# PiPico.net
KiCad netlist of a schematic drawn in Altium Designer
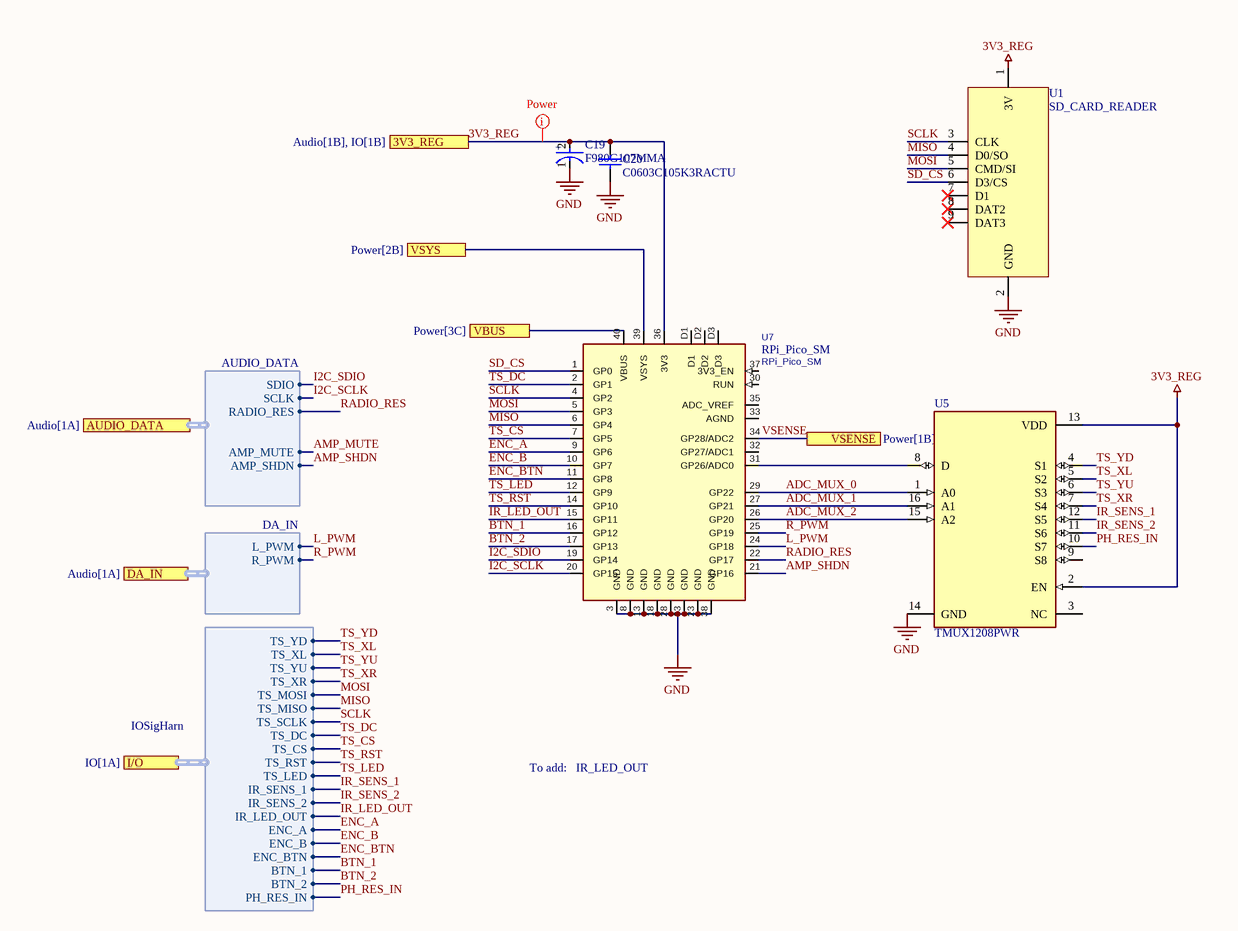
[diagram p0: PiPico.SchDoc]

(export (version "E")
  (design (tool "Eeschema 10.0.6"))
  (components
    (comp (ref "C19")
      (value "F980G107MMA")
      (footprint "FP-F98M-MFG")
      (description "CAP TANT 100UF 20% 4V 0603")
      (fields
        (field (name "OCTOPART") "https://octopart.com/f980g107mma-avx-28870482")
        (field (name "MANUFACTURER") "AVX Corporation")
      )
      (libsource (lib "Altium Content Vault") (part "cf48714ba7e38822c1575c7ec0b6d1f"))
    )
    (comp (ref "C20")
      (value "C0603C105K3RACTU")
      (footprint "CAPC1608X87X35LL15T15")
      (fields (field (name "MANUFACTURER") "Kemet"))
      (libsource (lib "Altium Content Vault") (part "CAP"))
    )
    (comp (ref "U1")
      (value "SD_CARD_READER")
      (footprint "6-pin Header (Generic)")
      (libsource (lib "ECE299_PCB") (part "SD_CARD_READER"))
    )
    (comp (ref "U5")
      (value "TMUX1208PWR")
      (footprint "FP-PW0016A-IPC_A")
      (description "IC SWITCH SINGLE 16TSSOP")
      (libsource (lib "Altium Content Vault") (part "3fc1eebd4caa5623a46538ca285a60d"))
    )
    (comp (ref "U7")
      (value "RPi_Pico_SM")
      (footprint "RPi_Pico_SM")
      (fields (field (name "ALTIUM_VALUE") "RPi_Pico_SM"))
      (libsource (lib "IlamStuff") (part "RPi_Pico_SM"))
    )
  )
  (nets
    (net (code "4") (name "/ADC_MUX_0") (class "Default")
      (node (ref "U5") (pin "1") (pinfunction "A0_1") (pintype "input"))
      (node (ref "U7") (pin "29") (pinfunction "GP22_29") (pintype "bidirectional"))
    )
    (net (code "5") (name "/ADC_MUX_1") (class "Default")
      (node (ref "U5") (pin "16") (pinfunction "A1_16") (pintype "input"))
      (node (ref "U7") (pin "27") (pinfunction "GP21_27") (pintype "bidirectional"))
    )
    (net (code "6") (name "/ADC_MUX_2") (class "Default")
      (node (ref "U5") (pin "15") (pinfunction "A2_15") (pintype "input"))
      (node (ref "U7") (pin "26") (pinfunction "GP20_26") (pintype "bidirectional"))
    )
    (net (code "8") (name "/AMP_SHDN") (class "Default")
      (node (ref "U7") (pin "21") (pinfunction "GP16_21") (pintype "bidirectional"))
    )
    (net (code "9") (name "/BTN_1") (class "Default")
      (node (ref "U7") (pin "16") (pinfunction "GP12_16") (pintype "bidirectional"))
    )
    (net (code "10") (name "/BTN_2") (class "Default")
      (node (ref "U7") (pin "17") (pinfunction "GP13_17") (pintype "bidirectional"))
    )
    (net (code "11") (name "/ENC_A") (class "Default")
      (node (ref "U7") (pin "9") (pinfunction "GP6_9") (pintype "bidirectional"))
    )
    (net (code "12") (name "/ENC_B") (class "Default")
      (node (ref "U7") (pin "10") (pinfunction "GP7_10") (pintype "bidirectional"))
    )
    (net (code "13") (name "/ENC_BTN") (class "Default")
      (node (ref "U7") (pin "11") (pinfunction "GP8_11") (pintype "bidirectional"))
    )
    (net (code "14") (name "/I2C_SCLK") (class "Default")
      (node (ref "U7") (pin "20") (pinfunction "GP15_20") (pintype "bidirectional"))
    )
    (net (code "15") (name "/I2C_SDIO") (class "Default")
      (node (ref "U7") (pin "19") (pinfunction "GP14_19") (pintype "bidirectional"))
    )
    (net (code "16") (name "/IR_LED_OUT") (class "Default")
      (node (ref "U7") (pin "15") (pinfunction "GP11_15") (pintype "bidirectional"))
    )
    (net (code "17") (name "/IR_SENS_1") (class "Default")
      (node (ref "U5") (pin "12") (pinfunction "S5_12") (pintype "bidirectional"))
    )
    (net (code "18") (name "/IR_SENS_2") (class "Default")
      (node (ref "U5") (pin "11") (pinfunction "S6_11") (pintype "bidirectional"))
    )
    (net (code "19") (name "/L_PWM") (class "Default")
      (node (ref "U7") (pin "24") (pinfunction "GP18_24") (pintype "bidirectional"))
    )
    (net (code "20") (name "/MISO") (class "Default")
      (node (ref "U1") (pin "4") (pinfunction "D0/SO_4") (pintype "passive"))
      (node (ref "U7") (pin "6") (pinfunction "GP4_6") (pintype "bidirectional"))
    )
    (net (code "21") (name "/MOSI") (class "Default")
      (node (ref "U1") (pin "5") (pinfunction "CMD/SI_5") (pintype "passive"))
      (node (ref "U7") (pin "5") (pinfunction "GP3_5") (pintype "bidirectional"))
    )
    (net (code "22") (name "/PH_RES_IN") (class "Default")
      (node (ref "U5") (pin "10") (pinfunction "S7_10") (pintype "bidirectional"))
    )
    (net (code "23") (name "/RADIO_RES") (class "Default")
      (node (ref "U7") (pin "22") (pinfunction "GP17_22") (pintype "bidirectional"))
    )
    (net (code "24") (name "/R_PWM") (class "Default")
      (node (ref "U7") (pin "25") (pinfunction "GP19_25") (pintype "bidirectional"))
    )
    (net (code "25") (name "/SCLK") (class "Default")
      (node (ref "U1") (pin "3") (pinfunction "CLK_3") (pintype "passive"))
      (node (ref "U7") (pin "4") (pinfunction "GP2_4") (pintype "bidirectional"))
    )
    (net (code "26") (name "/SD_CS") (class "Default")
      (node (ref "U1") (pin "6") (pinfunction "D3/CS_6") (pintype "passive"))
      (node (ref "U7") (pin "1") (pinfunction "GP0_1") (pintype "bidirectional"))
    )
    (net (code "27") (name "/TS_CS") (class "Default")
      (node (ref "U7") (pin "7") (pinfunction "GP5_7") (pintype "bidirectional"))
    )
    (net (code "28") (name "/TS_DC") (class "Default")
      (node (ref "U7") (pin "2") (pinfunction "GP1_2") (pintype "bidirectional"))
    )
    (net (code "29") (name "/TS_LED") (class "Default")
      (node (ref "U7") (pin "12") (pinfunction "GP9_12") (pintype "bidirectional"))
    )
    (net (code "30") (name "/TS_RST") (class "Default")
      (node (ref "U7") (pin "14") (pinfunction "GP10_14") (pintype "bidirectional"))
    )
    (net (code "31") (name "/TS_XL") (class "Default")
      (node (ref "U5") (pin "5") (pinfunction "S2_5") (pintype "bidirectional"))
    )
    (net (code "32") (name "/TS_XR") (class "Default")
      (node (ref "U5") (pin "7") (pinfunction "S4_7") (pintype "bidirectional"))
    )
    (net (code "33") (name "/TS_YD") (class "Default")
      (node (ref "U5") (pin "4") (pinfunction "S1_4") (pintype "bidirectional"))
    )
    (net (code "34") (name "/TS_YU") (class "Default")
      (node (ref "U5") (pin "6") (pinfunction "S3_6") (pintype "bidirectional"))
    )
    (net (code "35") (name "/VBUS") (class "Default")
      (node (ref "U7") (pin "40") (pinfunction "VBUS_40") (pintype "power_in"))
    )
    (net (code "36") (name "/VSENSE") (class "Default")
      (node (ref "U7") (pin "34") (pinfunction "GP28/ADC2_34") (pintype "bidirectional"))
    )
    (net (code "37") (name "/VSYS") (class "Default")
      (node (ref "U7") (pin "39") (pinfunction "VSYS_39") (pintype "power_in"))
    )
    (net (code "41") (name "3V3_REG") (class "Default")
      (node (ref "C19") (pin "2") (pinfunction "A_2") (pintype "passive"))
      (node (ref "C20") (pin "2") (pinfunction "2_2") (pintype "passive"))
      (node (ref "U1") (pin "1") (pinfunction "3V_1") (pintype "passive"))
      (node (ref "U5") (pin "13") (pinfunction "VDD_13") (pintype "power_in"))
      (node (ref "U5") (pin "2") (pinfunction "EN_2") (pintype "input"))
      (node (ref "U7") (pin "36") (pinfunction "3V3_36") (pintype "power_in"))
    )
    (net (code "42") (name "GND") (class "Default")
      (node (ref "C19") (pin "1") (pinfunction "C_1") (pintype "passive"))
      (node (ref "C20") (pin "1") (pinfunction "1_1") (pintype "passive"))
      (node (ref "U1") (pin "2") (pinfunction "GND_2") (pintype "passive"))
      (node (ref "U5") (pin "14") (pinfunction "GND_14") (pintype "power_in"))
      (node (ref "U7") (pin "13") (pinfunction "GND_13") (pintype "power_in"))
      (node (ref "U7") (pin "18") (pinfunction "GND_18") (pintype "power_in"))
      (node (ref "U7") (pin "23") (pinfunction "GND_23") (pintype "power_in"))
      (node (ref "U7") (pin "28") (pinfunction "GND_28") (pintype "power_in"))
      (node (ref "U7") (pin "3") (pinfunction "GND_3") (pintype "power_in"))
      (node (ref "U7") (pin "33") (pinfunction "GND_33") (pintype "power_in"))
      (node (ref "U7") (pin "38") (pinfunction "GND_38") (pintype "power_in"))
      (node (ref "U7") (pin "8") (pinfunction "GND_8") (pintype "power_in"))
    )
    (net (code "43") (name "Net-(U5-D)") (class "Default")
      (node (ref "U5") (pin "8") (pinfunction "D_8") (pintype "bidirectional"))
      (node (ref "U7") (pin "31") (pinfunction "GP26/ADC0_31") (pintype "bidirectional"))
    )
    (net (code "44") (name "unconnected-(U1-D1-Pad7)") (class "Default")
      (node (ref "U1") (pin "7") (pinfunction "D1_7") (pintype "passive+no_connect"))
    )
    (net (code "45") (name "unconnected-(U1-DAT2-Pad8)") (class "Default")
      (node (ref "U1") (pin "8") (pinfunction "DAT2_8") (pintype "passive+no_connect"))
    )
    (net (code "46") (name "unconnected-(U1-DAT3-Pad9)") (class "Default")
      (node (ref "U1") (pin "9") (pinfunction "DAT3_9") (pintype "passive+no_connect"))
    )
    (net (code "47") (name "unconnected-(U5-NC-Pad3)") (class "Default")
      (node (ref "U5") (pin "3") (pinfunction "NC_3") (pintype "passive"))
    )
    (net (code "48") (name "unconnected-(U5-S8-Pad9)") (class "Default")
      (node (ref "U5") (pin "9") (pinfunction "S8_9") (pintype "bidirectional"))
    )
    (net (code "49") (name "unconnected-(U7-3V3_EN-Pad37)") (class "Default")
      (node (ref "U7") (pin "37") (pinfunction "3V3_EN_37") (pintype "input"))
    )
    (net (code "50") (name "unconnected-(U7-ADC_VREF-Pad35)") (class "Default")
      (node (ref "U7") (pin "35") (pinfunction "ADC_VREF_35") (pintype "power_in"))
    )
    (net (code "51") (name "unconnected-(U7-AGND-Pad33)") (class "Default")
      (node (ref "U7") (pin "33") (pinfunction "AGND_33") (pintype "power_in"))
    )
    (net (code "52") (name "unconnected-(U7-GP27{slash}ADC1-Pad32)") (class "Default")
      (node (ref "U7") (pin "32") (pinfunction "GP27/ADC1_32") (pintype "bidirectional"))
    )
    (net (code "53") (name "unconnected-(U7-PadD1)") (class "Default")
      (node (ref "U7") (pin "D1") (pinfunction "D1_D1") (pintype "bidirectional"))
    )
    (net (code "54") (name "unconnected-(U7-PadD2)") (class "Default")
      (node (ref "U7") (pin "D2") (pinfunction "D2_D2") (pintype "bidirectional"))
    )
    (net (code "55") (name "unconnected-(U7-PadD3)") (class "Default")
      (node (ref "U7") (pin "D3") (pinfunction "D3_D3") (pintype "bidirectional"))
    )
    (net (code "56") (name "unconnected-(U7-RUN-Pad30)") (class "Default")
      (node (ref "U7") (pin "30") (pinfunction "RUN_30") (pintype "input"))
    )
  )
)
